# MainBoard.net
KiCad netlist of a schematic drawn in Altium Designer
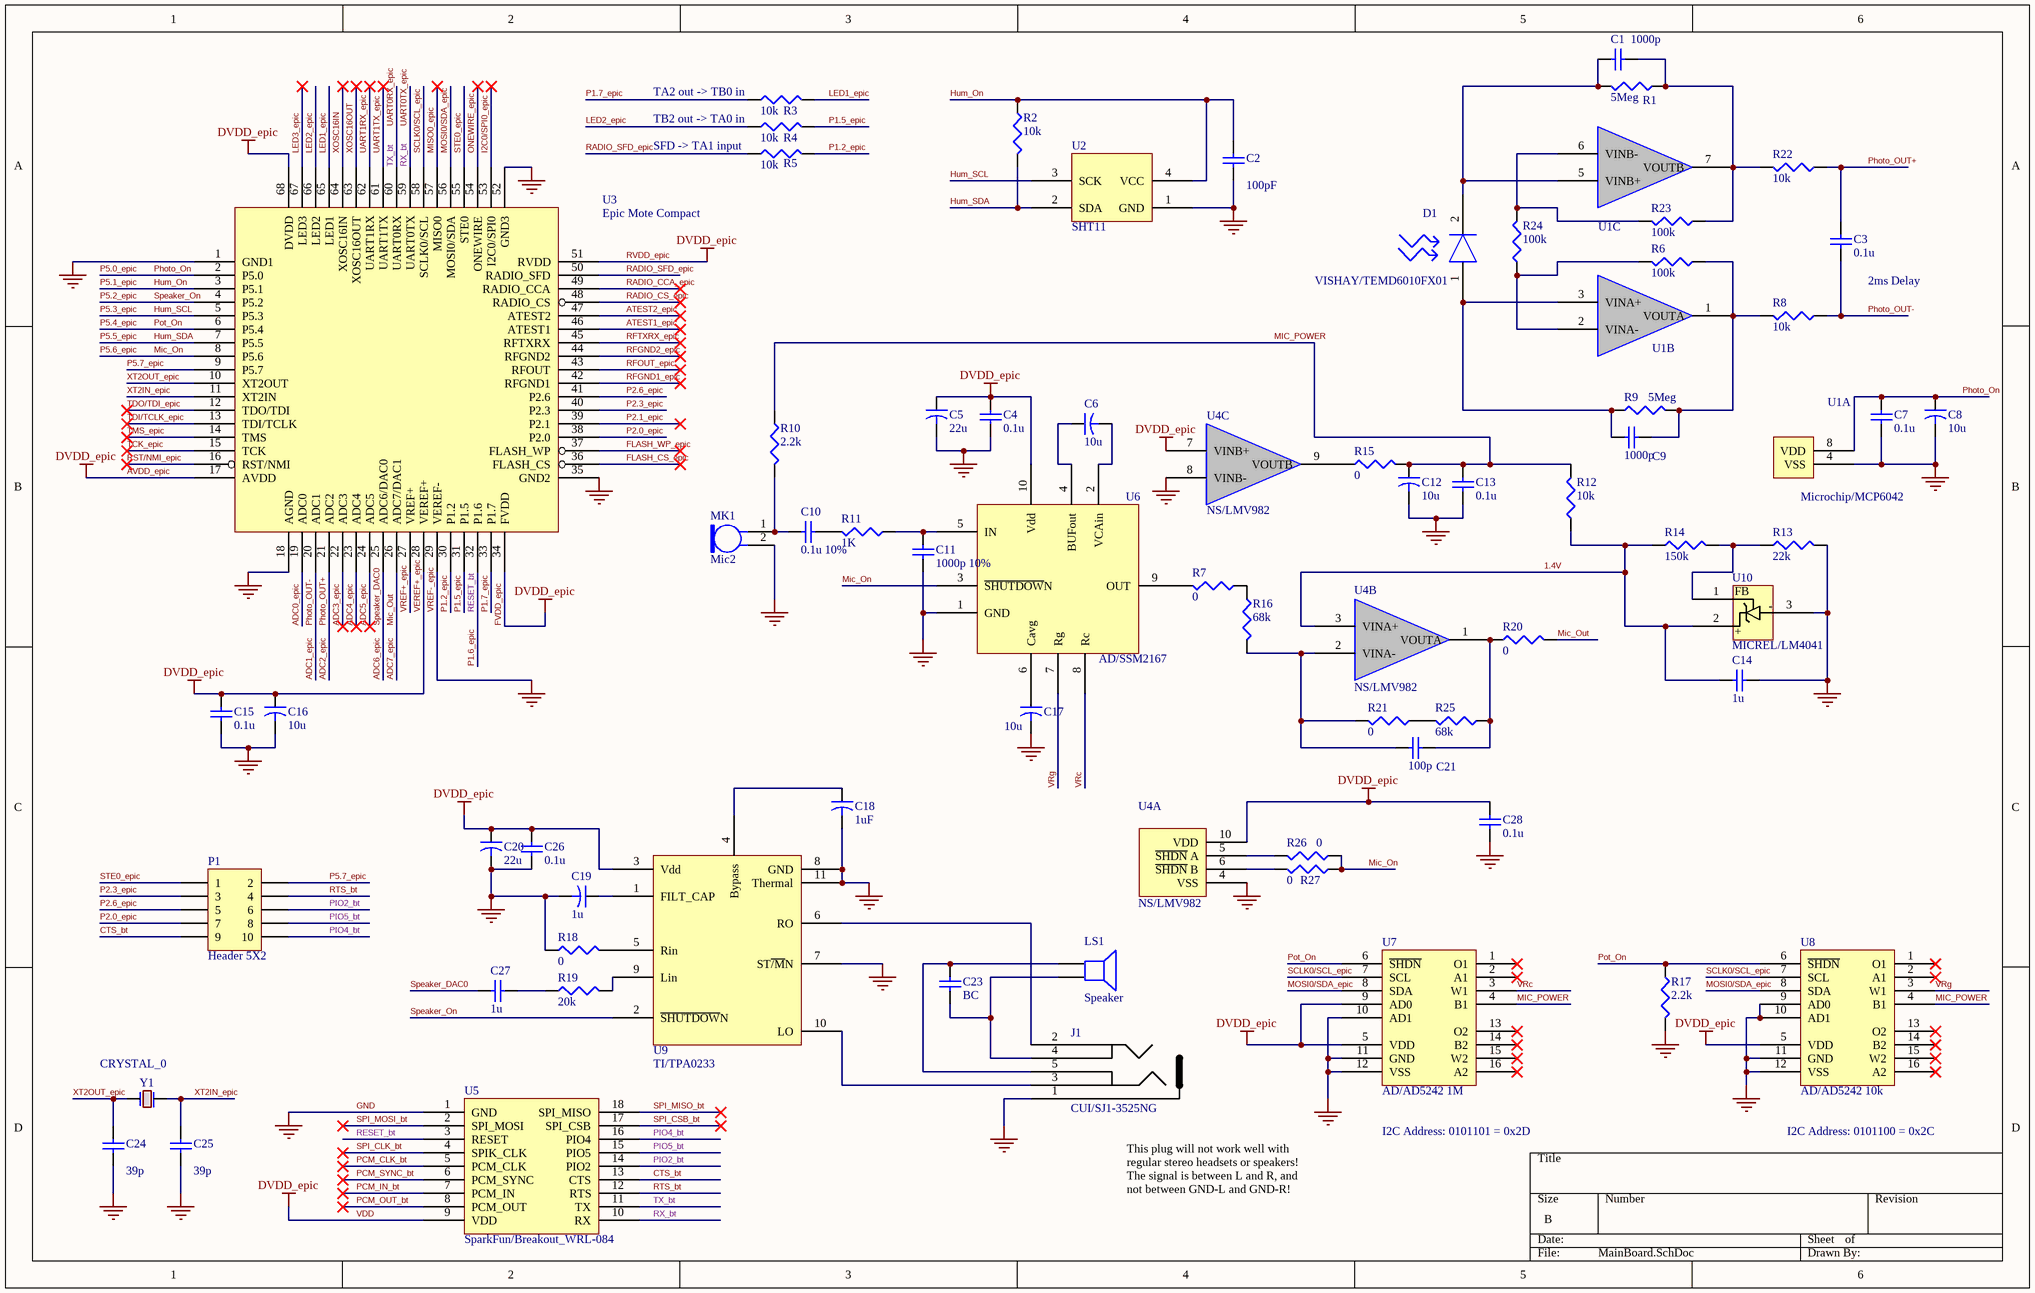
[diagram p0: MainBoard.SchDoc]

(export (version "E")
  (design (tool "Eeschema 10.0.6"))
  (components
    (comp (ref "C1")
      (value "1000p")
      (footprint "CC1608-0603")
      (description "Capacitor")
      (fields (field (name "Comment") "Cap") (field (name "PUBLISHER") "Altium Limited"))
      (libsource (lib "Miscellaneous Devices") (part "Cap"))
    )
    (comp (ref "C2")
      (value "100pF")
      (footprint "CC1608-0603")
      (description "Capacitor")
      (fields (field (name "Comment") "Cap") (field (name "PUBLISHER") "Altium Limited"))
      (libsource (lib "Miscellaneous Devices") (part "Cap"))
    )
    (comp (ref "C3")
      (value "0.1u")
      (footprint "CC1608-0603")
      (description "Capacitor")
      (fields (field (name "Comment") "Cap") (field (name "PUBLISHER") "Altium Limited"))
      (libsource (lib "Miscellaneous Devices") (part "Cap"))
    )
    (comp (ref "C4")
      (value "0.1u")
      (footprint "CC1608-0603")
      (description "Capacitor")
      (fields (field (name "Comment") "Cap") (field (name "PUBLISHER") "Altium Limited"))
      (libsource (lib "Miscellaneous Devices") (part "Cap"))
    )
    (comp (ref "C5")
      (value "22u")
      (footprint "CC3216-1206")
      (description "Capacitor")
      (fields (field (name "Comment") "Cap2") (field (name "PUBLISHER") "Altium Limited"))
      (libsource (lib "Miscellaneous Devices") (part "Cap2"))
    )
    (comp (ref "C6")
      (value "10u")
      (footprint "CC1608-0603")
      (description "Capacitor")
      (fields (field (name "Comment") "Cap2") (field (name "PUBLISHER") "Altium Limited"))
      (libsource (lib "") (part "Cap2_1"))
    )
    (comp (ref "C7")
      (value "0.1u")
      (footprint "CC1608-0603")
      (description "Capacitor")
      (fields (field (name "Comment") "Cap") (field (name "PUBLISHER") "Altium Limited"))
      (libsource (lib "Miscellaneous Devices") (part "Cap"))
    )
    (comp (ref "C8")
      (value "10u")
      (footprint "CC1608-0603")
      (description "Capacitor")
      (fields (field (name "Comment") "Cap2") (field (name "PUBLISHER") "Altium Limited"))
      (libsource (lib "Miscellaneous Devices") (part "Cap2"))
    )
    (comp (ref "C9")
      (value "1000p")
      (footprint "CC1608-0603")
      (description "Capacitor")
      (fields (field (name "Comment") "Cap") (field (name "PUBLISHER") "Altium Limited"))
      (libsource (lib "Miscellaneous Devices") (part "Cap"))
    )
    (comp (ref "C10")
      (value "0.1u 10%")
      (footprint "CC1608-0603")
      (description "Capacitor")
      (fields (field (name "Comment") "Cap") (field (name "PUBLISHER") "Altium Limited"))
      (libsource (lib "Miscellaneous Devices") (part "Cap"))
    )
    (comp (ref "C11")
      (value "1000p 10%")
      (footprint "CC1608-0603")
      (description "Capacitor")
      (fields (field (name "Comment") "Cap") (field (name "PUBLISHER") "Altium Limited"))
      (libsource (lib "Miscellaneous Devices") (part "Cap"))
    )
    (comp (ref "C12")
      (value "10u")
      (footprint "CC1608-0603")
      (description "Capacitor")
      (fields (field (name "Comment") "Cap2") (field (name "PUBLISHER") "Altium Limited"))
      (libsource (lib "Miscellaneous Devices") (part "Cap2"))
    )
    (comp (ref "C13")
      (value "0.1u")
      (footprint "CC1608-0603")
      (description "Capacitor")
      (fields (field (name "Comment") "Cap") (field (name "PUBLISHER") "Altium Limited"))
      (libsource (lib "Miscellaneous Devices") (part "Cap"))
    )
    (comp (ref "C14")
      (value "1u")
      (footprint "CC1608-0603")
      (description "Capacitor")
      (fields (field (name "Comment") "Cap") (field (name "PUBLISHER") "Altium Limited"))
      (libsource (lib "") (part "Cap_1"))
    )
    (comp (ref "C15")
      (value "0.1u")
      (footprint "CC1608-0603")
      (description "Capacitor")
      (fields (field (name "Comment") "Cap") (field (name "PUBLISHER") "Altium Limited"))
      (libsource (lib "Miscellaneous Devices") (part "Cap"))
    )
    (comp (ref "C16")
      (value "10u")
      (footprint "CC1608-0603")
      (description "Capacitor")
      (fields (field (name "Comment") "Cap2") (field (name "PUBLISHER") "Altium Limited"))
      (libsource (lib "Miscellaneous Devices") (part "Cap2"))
    )
    (comp (ref "C17")
      (value "10u")
      (footprint "CC1608-0603")
      (description "Capacitor")
      (fields (field (name "Comment") "Cap2") (field (name "PUBLISHER") "Altium Limited"))
      (libsource (lib "") (part "Cap2_1"))
    )
    (comp (ref "C18")
      (value "1uF")
      (footprint "CC1608-0603")
      (description "Capacitor")
      (fields (field (name "Comment") "Cap2") (field (name "PUBLISHER") "Altium Limited"))
      (libsource (lib "") (part "Cap2_1"))
    )
    (comp (ref "C19")
      (value "1u")
      (footprint "CC1608-0603")
      (description "Capacitor")
      (fields (field (name "Comment") "Cap2") (field (name "PUBLISHER") "Altium Limited"))
      (libsource (lib "") (part "Cap2_1"))
    )
    (comp (ref "C20")
      (value "22u")
      (footprint "CC3216-1206")
      (description "Capacitor")
      (fields (field (name "Comment") "Cap2") (field (name "PUBLISHER") "Altium Limited"))
      (libsource (lib "Miscellaneous Devices") (part "Cap2"))
    )
    (comp (ref "C21")
      (value "100p")
      (footprint "CC1608-0603")
      (description "Capacitor")
      (fields (field (name "Comment") "Cap") (field (name "PUBLISHER") "Altium Limited"))
      (libsource (lib "Miscellaneous Devices") (part "Cap"))
    )
    (comp (ref "C23")
      (value "BC")
      (footprint "CC1608-0603")
      (description "Capacitor")
      (fields (field (name "Comment") "Cap") (field (name "PUBLISHER") "Altium Limited"))
      (libsource (lib "Miscellaneous Devices") (part "Cap"))
    )
    (comp (ref "C24")
      (value "39p")
      (footprint "CC1608-0603")
      (description "Capacitor")
      (fields (field (name "Comment") "Cap") (field (name "PUBLISHER") "Altium Limited"))
      (libsource (lib "Miscellaneous Devices") (part "Cap"))
    )
    (comp (ref "C25")
      (value "39p")
      (footprint "CC1608-0603")
      (description "Capacitor")
      (fields (field (name "Comment") "Cap") (field (name "PUBLISHER") "Altium Limited"))
      (libsource (lib "Miscellaneous Devices") (part "Cap"))
    )
    (comp (ref "C26")
      (value "0.1u")
      (footprint "CC1608-0603")
      (description "Capacitor")
      (fields (field (name "Comment") "Cap") (field (name "PUBLISHER") "Altium Limited"))
      (libsource (lib "Miscellaneous Devices") (part "Cap"))
    )
    (comp (ref "C27")
      (value "1u")
      (footprint "CC1608-0603")
      (description "Capacitor")
      (fields (field (name "Comment") "Cap") (field (name "PUBLISHER") "Altium Limited"))
      (libsource (lib "Miscellaneous Devices") (part "Cap"))
    )
    (comp (ref "C28")
      (value "0.1u")
      (footprint "CC1608-0603")
      (description "Capacitor")
      (fields (field (name "Comment") "Cap") (field (name "PUBLISHER") "Altium Limited"))
      (libsource (lib "Miscellaneous Devices") (part "Cap"))
    )
    (comp (ref "D1")
      (value "VISHAY/TEMD6010FX01")
      (footprint "VISHAY/TEMD6010FX01")
      (libsource (lib "Schematics") (part "VISHAY/TEMD6010FX01"))
    )
    (comp (ref "J1")
      (value "CUI/SJ1-3525NG")
      (footprint "CUI/PHONE_JACK_3.5mm")
      (libsource (lib "Schematics") (part "CUI/SJ1-3525NG"))
    )
    (comp (ref "LS1")
      (value "Speaker")
      (footprint "PIN2")
      (description "Loudspeaker")
      (fields (field (name "PUBLISHER") "Altium Limited"))
      (libsource (lib "Miscellaneous Devices") (part "Speaker"))
    )
    (comp (ref "MK1")
      (value "Mic2")
      (footprint "CUIINC/CMA-4544PF-W")
      (description "Microphone")
      (fields (field (name "PUBLISHER") "Altium Limited"))
      (libsource (lib "Miscellaneous Devices") (part "Mic2"))
    )
    (comp (ref "P1")
      (value "Header 5X2")
      (footprint "HDR2X5")
      (description "Header, 5-Pin, Dual row")
      (fields (field (name "PUBLISHER") "Altium Limited"))
      (libsource (lib "Miscellaneous Connectors") (part "Header 5X2"))
    )
    (comp (ref "R1")
      (value "5Meg")
      (footprint "CR1608-0603")
      (description "Resistor")
      (fields (field (name "Comment") "Res3") (field (name "PUBLISHER") "Altium Limited"))
      (libsource (lib "Miscellaneous Devices") (part "Res3"))
    )
    (comp (ref "R2")
      (value "10k")
      (footprint "CR1608-0603")
      (description "Resistor")
      (fields (field (name "Comment") "Res3") (field (name "PUBLISHER") "Altium Limited"))
      (libsource (lib "Miscellaneous Devices") (part "Res3"))
    )
    (comp (ref "R3")
      (value "10k")
      (footprint "CR1608-0603")
      (description "Resistor")
      (fields (field (name "Comment") "Res3") (field (name "PUBLISHER") "Altium Limited"))
      (libsource (lib "Miscellaneous Devices") (part "Res3"))
    )
    (comp (ref "R4")
      (value "10k")
      (footprint "CR1608-0603")
      (description "Resistor")
      (fields (field (name "Comment") "Res3") (field (name "PUBLISHER") "Altium Limited"))
      (libsource (lib "Miscellaneous Devices") (part "Res3"))
    )
    (comp (ref "R5")
      (value "10k")
      (footprint "CR1608-0603")
      (description "Resistor")
      (fields (field (name "Comment") "Res3") (field (name "PUBLISHER") "Altium Limited"))
      (libsource (lib "Miscellaneous Devices") (part "Res3"))
    )
    (comp (ref "R6")
      (value "100k")
      (footprint "CR1608-0603")
      (description "Resistor")
      (fields (field (name "Comment") "Res3") (field (name "PUBLISHER") "Altium Limited"))
      (libsource (lib "Miscellaneous Devices") (part "Res3"))
    )
    (comp (ref "R7")
      (value "0")
      (footprint "CR1608-0603")
      (description "Resistor")
      (fields (field (name "Comment") "Res3") (field (name "PUBLISHER") "Altium Limited"))
      (libsource (lib "Miscellaneous Devices") (part "Res3"))
    )
    (comp (ref "R8")
      (value "10k")
      (footprint "CR1608-0603")
      (description "Resistor")
      (fields (field (name "Comment") "Res3") (field (name "PUBLISHER") "Altium Limited"))
      (libsource (lib "Miscellaneous Devices") (part "Res3"))
    )
    (comp (ref "R9")
      (value "5Meg")
      (footprint "CR1608-0603")
      (description "Resistor")
      (fields (field (name "Comment") "Res3") (field (name "PUBLISHER") "Altium Limited"))
      (libsource (lib "Miscellaneous Devices") (part "Res3"))
    )
    (comp (ref "R10")
      (value "2.2k")
      (footprint "CR1608-0603")
      (description "Resistor")
      (fields (field (name "Comment") "Res3") (field (name "PUBLISHER") "Altium Limited"))
      (libsource (lib "Miscellaneous Devices") (part "Res3"))
    )
    (comp (ref "R11")
      (value "1K")
      (footprint "CR1608-0603")
      (description "Resistor")
      (fields (field (name "Comment") "Res3") (field (name "PUBLISHER") "Altium Limited"))
      (libsource (lib "Miscellaneous Devices") (part "Res3"))
    )
    (comp (ref "R12")
      (value "10k")
      (footprint "CR1608-0603")
      (description "Resistor")
      (fields (field (name "Comment") "Res3") (field (name "PUBLISHER") "Altium Limited"))
      (libsource (lib "Miscellaneous Devices") (part "Res3"))
    )
    (comp (ref "R13")
      (value "22k")
      (footprint "CR1608-0603")
      (description "Resistor")
      (fields (field (name "Comment") "Res3") (field (name "PUBLISHER") "Altium Limited"))
      (libsource (lib "Miscellaneous Devices") (part "Res3"))
    )
    (comp (ref "R14")
      (value "150k")
      (footprint "CR1608-0603")
      (description "Resistor")
      (fields (field (name "Comment") "Res3") (field (name "PUBLISHER") "Altium Limited"))
      (libsource (lib "Miscellaneous Devices") (part "Res3"))
    )
    (comp (ref "R15")
      (value "0")
      (footprint "CR1608-0603")
      (description "Resistor")
      (fields (field (name "Comment") "Res3") (field (name "PUBLISHER") "Altium Limited"))
      (libsource (lib "Miscellaneous Devices") (part "Res3"))
    )
    (comp (ref "R16")
      (value "68k")
      (footprint "CR1608-0603")
      (description "Resistor")
      (fields (field (name "Comment") "Res3") (field (name "PUBLISHER") "Altium Limited"))
      (libsource (lib "") (part "Res3_1"))
    )
    (comp (ref "R17")
      (value "2.2k")
      (footprint "CR1608-0603")
      (description "Resistor")
      (fields (field (name "Comment") "Res3") (field (name "PUBLISHER") "Altium Limited"))
      (libsource (lib "Miscellaneous Devices") (part "Res3"))
    )
    (comp (ref "R18")
      (value "0")
      (footprint "CR1608-0603")
      (description "Resistor")
      (fields (field (name "Comment") "Res3") (field (name "PUBLISHER") "Altium Limited"))
      (libsource (lib "Miscellaneous Devices") (part "Res3"))
    )
    (comp (ref "R19")
      (value "20k")
      (footprint "CR1608-0603")
      (description "Resistor")
      (fields (field (name "Comment") "Res3") (field (name "PUBLISHER") "Altium Limited"))
      (libsource (lib "Miscellaneous Devices") (part "Res3"))
    )
    (comp (ref "R20")
      (value "0")
      (footprint "CR1608-0603")
      (description "Resistor")
      (fields (field (name "Comment") "Res3") (field (name "PUBLISHER") "Altium Limited"))
      (libsource (lib "Miscellaneous Devices") (part "Res3"))
    )
    (comp (ref "R21")
      (value "0")
      (footprint "CR1608-0603")
      (description "Resistor")
      (fields (field (name "Comment") "Res3") (field (name "PUBLISHER") "Altium Limited"))
      (libsource (lib "Miscellaneous Devices") (part "Res3"))
    )
    (comp (ref "R22")
      (value "10k")
      (footprint "CR1608-0603")
      (description "Resistor")
      (fields (field (name "Comment") "Res3") (field (name "PUBLISHER") "Altium Limited"))
      (libsource (lib "Miscellaneous Devices") (part "Res3"))
    )
    (comp (ref "R23")
      (value "100k")
      (footprint "CR1608-0603")
      (description "Resistor")
      (fields (field (name "Comment") "Res3") (field (name "PUBLISHER") "Altium Limited"))
      (libsource (lib "Miscellaneous Devices") (part "Res3"))
    )
    (comp (ref "R24")
      (value "100k")
      (footprint "CR1608-0603")
      (description "Resistor")
      (fields (field (name "Comment") "Res3") (field (name "PUBLISHER") "Altium Limited"))
      (libsource (lib "Miscellaneous Devices") (part "Res3"))
    )
    (comp (ref "R25")
      (value "68k")
      (footprint "CR1608-0603")
      (description "Resistor")
      (fields (field (name "Comment") "Res3") (field (name "PUBLISHER") "Altium Limited"))
      (libsource (lib "Miscellaneous Devices") (part "Res3"))
    )
    (comp (ref "R26")
      (value "0")
      (footprint "CR1608-0603")
      (description "Resistor")
      (fields (field (name "Comment") "Res3") (field (name "PUBLISHER") "Altium Limited"))
      (libsource (lib "Miscellaneous Devices") (part "Res3"))
    )
    (comp (ref "R27")
      (value "0")
      (footprint "CR1608-0603")
      (description "Resistor")
      (fields (field (name "Comment") "Res3") (field (name "PUBLISHER") "Altium Limited"))
      (libsource (lib "Miscellaneous Devices") (part "Res3"))
    )
    (comp (ref "U1")
      (value "Microchip/MCP6042")
      (footprint "SOIC127P600X175-8N")
      (libsource (lib "Schematics") (part "Microchip/MCP6042"))
    )
    (comp (ref "U2")
      (value "SHT11")
      (footprint "Sensirion/SHT11")
      (libsource (lib "Schematics") (part "SHT11"))
    )
    (comp (ref "U3")
      (value "Epic Mote Compact")
      (footprint "UCB/Epic_Quanto_Header")
      (libsource (lib "Schematics") (part "Epic Mote Compact"))
    )
    (comp (ref "U4")
      (value "NS/LMV982")
      (footprint "MSOP10")
      (libsource (lib "Schematics") (part "NS/LMV982"))
    )
    (comp (ref "U5")
      (value "SparkFun/Breakout_WRL-084")
      (footprint "SparkFun/Breakout_WRL-084")
      (libsource (lib "Schematics") (part "SparkFun/Breakout_WRL-084"))
    )
    (comp (ref "U6")
      (value "AD/SSM2167")
      (footprint "MSOP127P600-8N")
      (libsource (lib "Schematics") (part "AD/SSM2167"))
    )
    (comp (ref "U7")
      (value "AD/AD5242 1M")
      (footprint "SOIC127P600X175-16N")
      (libsource (lib "Schematics") (part "AD/AD5242"))
    )
    (comp (ref "U8")
      (value "AD/AD5242 10k")
      (footprint "SOIC127P600X175-16N")
      (libsource (lib "Schematics") (part "AD/AD5242"))
    )
    (comp (ref "U9")
      (value "TI/TPA0233")
      (footprint "TSSOP50P480X107_HS-10N")
      (libsource (lib "Schematics") (part "TI/TPA0233"))
    )
    (comp (ref "U10")
      (value "MICREL/LM4041")
      (footprint "SOT231 (M3)")
      (libsource (lib "Schematics") (part "MICREL/LM4041"))
    )
    (comp (ref "Y1")
      (value "CRYSTAL_0")
      (footprint "ECS/CSM-7SSX")
      (libsource (lib "Schematics") (part "CRYSTAL_0"))
    )
  )
  (nets
    (net (code "1") (name "/1.4V") (class "Default")
      (node (ref "C14") (pin "1") (pinfunction "1_1") (pintype "passive"))
      (node (ref "R12") (pin "1") (pinfunction "1_1") (pintype "passive"))
      (node (ref "R14") (pin "1") (pinfunction "1_1") (pintype "passive"))
      (node (ref "U10") (pin "2") (pinfunction "2_2") (pintype "passive"))
      (node (ref "U4") (pin "3") (pinfunction "VINA+_3") (pintype "passive"))
    )
    (net (code "2") (name "/ADC0_epic") (class "Default")
      (node (ref "U3") (pin "19") (pinfunction "ADC0_19") (pintype "passive"))
    )
    (net (code "3") (name "/ADC1_epic") (class "Default")
      (node (ref "C3") (pin "2") (pinfunction "2_2") (pintype "passive"))
      (node (ref "R8") (pin "1") (pinfunction "1_1") (pintype "passive"))
      (node (ref "U3") (pin "20") (pinfunction "ADC1_20") (pintype "passive"))
    )
    (net (code "4") (name "/ADC2_epic") (class "Default")
      (node (ref "C3") (pin "1") (pinfunction "1_1") (pintype "passive"))
      (node (ref "R22") (pin "1") (pinfunction "1_1") (pintype "passive"))
      (node (ref "U3") (pin "21") (pinfunction "ADC2_21") (pintype "passive"))
    )
    (net (code "5") (name "/ADC3_epic") (class "Default")
      (node (ref "U3") (pin "22") (pinfunction "ADC3_22") (pintype "passive+no_connect"))
    )
    (net (code "6") (name "/ADC4_epic") (class "Default")
      (node (ref "U3") (pin "23") (pinfunction "ADC4_23") (pintype "passive+no_connect"))
    )
    (net (code "7") (name "/ADC5_epic") (class "Default")
      (node (ref "U3") (pin "24") (pinfunction "ADC5_24") (pintype "passive+no_connect"))
    )
    (net (code "8") (name "/ADC6_epic") (class "Default")
      (node (ref "C27") (pin "2") (pinfunction "2_2") (pintype "passive"))
      (node (ref "U3") (pin "25") (pinfunction "ADC6/DAC0_25") (pintype "passive"))
    )
    (net (code "9") (name "/ADC7_epic") (class "Default")
      (node (ref "R20") (pin "2") (pinfunction "2_2") (pintype "passive"))
      (node (ref "U3") (pin "26") (pinfunction "ADC7/DAC1_26") (pintype "passive"))
    )
    (net (code "10") (name "/ATEST1_epic") (class "Default")
      (node (ref "U3") (pin "46") (pinfunction "ATEST1_46") (pintype "passive+no_connect"))
    )
    (net (code "11") (name "/ATEST2_epic") (class "Default")
      (node (ref "U3") (pin "47") (pinfunction "ATEST2_47") (pintype "passive+no_connect"))
    )
    (net (code "12") (name "/CTS_bt") (class "Default")
      (node (ref "P1") (pin "9") (pinfunction "9_9") (pintype "passive"))
      (node (ref "U5") (pin "13") (pinfunction "CTS_13") (pintype "passive"))
    )
    (net (code "13") (name "/FLASH_CS_epic") (class "Default")
      (node (ref "U3") (pin "36") (pinfunction "FLASH_CS_36") (pintype "passive+no_connect"))
    )
    (net (code "14") (name "/FLASH_WP_epic") (class "Default")
      (node (ref "U3") (pin "37") (pinfunction "FLASH_WP_37") (pintype "passive+no_connect"))
    )
    (net (code "15") (name "/Hum_On") (class "Default")
      (node (ref "C2") (pin "2") (pinfunction "2_2") (pintype "passive"))
      (node (ref "R2") (pin "1") (pinfunction "1_1") (pintype "passive"))
      (node (ref "U2") (pin "4") (pinfunction "VCC_4") (pintype "power_in"))
      (node (ref "U3") (pin "3") (pinfunction "P5.1_3") (pintype "passive"))
    )
    (net (code "16") (name "/Hum_SCL") (class "Default")
      (node (ref "U2") (pin "3") (pinfunction "SCK_3") (pintype "passive"))
      (node (ref "U3") (pin "5") (pinfunction "P5.3_5") (pintype "passive"))
    )
    (net (code "17") (name "/Hum_SDA") (class "Default")
      (node (ref "R2") (pin "2") (pinfunction "2_2") (pintype "passive"))
      (node (ref "U2") (pin "2") (pinfunction "SDA_2") (pintype "passive"))
      (node (ref "U3") (pin "7") (pinfunction "P5.5_7") (pintype "passive"))
    )
    (net (code "18") (name "/I2C0{slash}SPI0_epic") (class "Default")
      (node (ref "U3") (pin "53") (pinfunction "I2C0/SPI0_53") (pintype "passive+no_connect"))
    )
    (net (code "19") (name "/LED1_epic") (class "Default")
      (node (ref "R3") (pin "2") (pinfunction "2_2") (pintype "passive"))
      (node (ref "U3") (pin "65") (pinfunction "LED1_65") (pintype "passive"))
    )
    (net (code "20") (name "/LED2_epic") (class "Default")
      (node (ref "R4") (pin "1") (pinfunction "1_1") (pintype "passive"))
      (node (ref "U3") (pin "66") (pinfunction "LED2_66") (pintype "passive"))
    )
    (net (code "21") (name "/LED3_epic") (class "Default")
      (node (ref "U3") (pin "67") (pinfunction "LED3_67") (pintype "passive+no_connect"))
    )
    (net (code "22") (name "/MIC_POWER") (class "Default")
      (node (ref "C12") (pin "1") (pinfunction "1_1") (pintype "passive"))
      (node (ref "C13") (pin "1") (pinfunction "1_1") (pintype "passive"))
      (node (ref "R10") (pin "1") (pinfunction "1_1") (pintype "passive"))
      (node (ref "R12") (pin "2") (pinfunction "2_2") (pintype "passive"))
      (node (ref "R15") (pin "2") (pinfunction "2_2") (pintype "passive"))
      (node (ref "U7") (pin "4") (pinfunction "B1_4") (pintype "passive"))
      (node (ref "U8") (pin "4") (pinfunction "B1_4") (pintype "passive"))
    )
    (net (code "23") (name "/MISO0_epic") (class "Default")
      (node (ref "U3") (pin "57") (pinfunction "MISO0_57") (pintype "passive+no_connect"))
    )
    (net (code "24") (name "/MOSI0{slash}SDA_epic") (class "Default")
      (node (ref "U3") (pin "56") (pinfunction "MOSI0/SDA_56") (pintype "passive"))
      (node (ref "U7") (pin "8") (pinfunction "SDA_8") (pintype "passive"))
      (node (ref "U8") (pin "8") (pinfunction "SDA_8") (pintype "passive"))
    )
    (net (code "25") (name "/Mic_On") (class "Default")
      (node (ref "R26") (pin "2") (pinfunction "2_2") (pintype "passive"))
      (node (ref "R27") (pin "2") (pinfunction "2_2") (pintype "passive"))
      (node (ref "U3") (pin "8") (pinfunction "P5.6_8") (pintype "passive"))
      (node (ref "U6") (pin "3") (pinfunction "~{SHUTDOW}N_3") (pintype "passive"))
    )
    (net (code "26") (name "/ONEWIRE_epic") (class "Default")
      (node (ref "U3") (pin "54") (pinfunction "ONEWIRE_54") (pintype "passive+no_connect"))
    )
    (net (code "27") (name "/P1.2_epic") (class "Default")
      (node (ref "R5") (pin "2") (pinfunction "2_2") (pintype "passive"))
      (node (ref "U3") (pin "30") (pinfunction "P1.2_30") (pintype "passive"))
    )
    (net (code "28") (name "/P1.5_epic") (class "Default")
      (node (ref "R4") (pin "2") (pinfunction "2_2") (pintype "passive"))
      (node (ref "U3") (pin "31") (pinfunction "P1.5_31") (pintype "passive"))
    )
    (net (code "29") (name "/P1.6_epic") (class "Default")
      (node (ref "U3") (pin "32") (pinfunction "P1.6_32") (pintype "passive"))
      (node (ref "U5") (pin "3") (pinfunction "RESET_3") (pintype "passive"))
    )
    (net (code "30") (name "/P1.7_epic") (class "Default")
      (node (ref "R3") (pin "1") (pinfunction "1_1") (pintype "passive"))
      (node (ref "U3") (pin "33") (pinfunction "P1.7_33") (pintype "passive"))
    )
    (net (code "31") (name "/P2.0_epic") (class "Default")
      (node (ref "P1") (pin "7") (pinfunction "7_7") (pintype "passive"))
      (node (ref "U3") (pin "38") (pinfunction "P2.0_38") (pintype "passive"))
    )
    (net (code "32") (name "/P2.1_epic") (class "Default")
      (node (ref "U3") (pin "39") (pinfunction "P2.1_39") (pintype "passive+no_connect"))
    )
    (net (code "33") (name "/P2.3_epic") (class "Default")
      (node (ref "P1") (pin "3") (pinfunction "3_3") (pintype "passive"))
      (node (ref "U3") (pin "40") (pinfunction "P2.3_40") (pintype "passive"))
    )
    (net (code "34") (name "/P2.6_epic") (class "Default")
      (node (ref "P1") (pin "5") (pinfunction "5_5") (pintype "passive"))
      (node (ref "U3") (pin "41") (pinfunction "P2.6_41") (pintype "passive"))
    )
    (net (code "35") (name "/P5.0_epic") (class "Default")
      (node (ref "C7") (pin "1") (pinfunction "1_1") (pintype "passive"))
      (node (ref "C8") (pin "1") (pinfunction "1_1") (pintype "passive"))
      (node (ref "U1") (pin "8") (pinfunction "VDD_8") (pintype "power_in"))
      (node (ref "U3") (pin "2") (pinfunction "P5.0_2") (pintype "passive"))
    )
    (net (code "36") (name "/P5.2_epic") (class "Default")
      (node (ref "U3") (pin "4") (pinfunction "P5.2_4") (pintype "passive"))
      (node (ref "U9") (pin "2") (pinfunction "~{SHUTDOW}N_2") (pintype "passive"))
    )
    (net (code "37") (name "/P5.4_epic") (class "Default")
      (node (ref "R17") (pin "1") (pinfunction "1_1") (pintype "passive"))
      (node (ref "U3") (pin "6") (pinfunction "P5.4_6") (pintype "passive"))
      (node (ref "U7") (pin "6") (pinfunction "~{SHDN}_6") (pintype "passive"))
      (node (ref "U8") (pin "6") (pinfunction "~{SHDN}_6") (pintype "passive"))
    )
    (net (code "38") (name "/P5.7_epic") (class "Default")
      (node (ref "P1") (pin "2") (pinfunction "2_2") (pintype "passive"))
      (node (ref "U3") (pin "9") (pinfunction "P5.7_9") (pintype "passive"))
    )
    (net (code "39") (name "/PCM_CLK_bt") (class "Default")
      (node (ref "U5") (pin "5") (pinfunction "PCM_CLK_5") (pintype "passive+no_connect"))
    )
    (net (code "40") (name "/PCM_IN_bt") (class "Default")
      (node (ref "U5") (pin "7") (pinfunction "PCM_IN_7") (pintype "passive+no_connect"))
    )
    (net (code "41") (name "/PCM_OUT_bt") (class "Default")
      (node (ref "U5") (pin "8") (pinfunction "PCM_OUT_8") (pintype "passive+no_connect"))
    )
    (net (code "42") (name "/PCM_SYNC_bt") (class "Default")
      (node (ref "U5") (pin "6") (pinfunction "PCM_SYNC_6") (pintype "passive+no_connect"))
    )
    (net (code "43") (name "/PIO2_bt") (class "Default")
      (node (ref "P1") (pin "6") (pinfunction "6_6") (pintype "passive"))
      (node (ref "U5") (pin "14") (pinfunction "PIO2_14") (pintype "passive"))
    )
    (net (code "44") (name "/PIO4_bt") (class "Default")
      (node (ref "P1") (pin "10") (pinfunction "10_10") (pintype "passive"))
      (node (ref "U5") (pin "16") (pinfunction "PIO4_16") (pintype "passive"))
    )
    (net (code "45") (name "/PIO5_bt") (class "Default")
      (node (ref "P1") (pin "8") (pinfunction "8_8") (pintype "passive"))
      (node (ref "U5") (pin "15") (pinfunction "PIO5_15") (pintype "passive"))
    )
    (net (code "46") (name "/RADIO_CCA_epic") (class "Default")
      (node (ref "U3") (pin "49") (pinfunction "RADIO_CCA_49") (pintype "passive+no_connect"))
    )
    (net (code "47") (name "/RADIO_CS_epic") (class "Default")
      (node (ref "U3") (pin "48") (pinfunction "RADIO_CS_48") (pintype "passive+no_connect"))
    )
    (net (code "48") (name "/RADIO_SFD_epic") (class "Default")
      (node (ref "R5") (pin "1") (pinfunction "1_1") (pintype "passive"))
      (node (ref "U3") (pin "50") (pinfunction "RADIO_SFD_50") (pintype "passive"))
    )
    (net (code "49") (name "/RFGND1_epic") (class "Default")
      (node (ref "U3") (pin "42") (pinfunction "RFGND1_42") (pintype "passive+no_connect"))
    )
    (net (code "50") (name "/RFGND2_epic") (class "Default")
      (node (ref "U3") (pin "44") (pinfunction "RFGND2_44") (pintype "passive+no_connect"))
    )
    (net (code "51") (name "/RFOUT_epic") (class "Default")
      (node (ref "U3") (pin "43") (pinfunction "RFOUT_43") (pintype "passive+no_connect"))
    )
    (net (code "52") (name "/RFTXRX_epic") (class "Default")
      (node (ref "U3") (pin "45") (pinfunction "RFTXRX_45") (pintype "passive+no_connect"))
    )
    (net (code "53") (name "/RST{slash}NMI_epic") (class "Default")
      (node (ref "U3") (pin "16") (pinfunction "RST/NMI_16") (pintype "passive+no_connect"))
    )
    (net (code "54") (name "/RTS_bt") (class "Default")
      (node (ref "P1") (pin "4") (pinfunction "4_4") (pintype "passive"))
      (node (ref "U5") (pin "12") (pinfunction "RTS_12") (pintype "passive"))
    )
    (net (code "55") (name "/RX_bt") (class "Default")
      (node (ref "U3") (pin "59") (pinfunction "UART0TX_59") (pintype "passive"))
      (node (ref "U5") (pin "10") (pinfunction "RX_10") (pintype "passive"))
    )
    (net (code "56") (name "/SCLK0{slash}SCL_epic") (class "Default")
      (node (ref "U3") (pin "58") (pinfunction "SCLK0/SCL_58") (pintype "passive"))
      (node (ref "U7") (pin "7") (pinfunction "SCL_7") (pintype "passive"))
      (node (ref "U8") (pin "7") (pinfunction "SCL_7") (pintype "passive"))
    )
    (net (code "57") (name "/SPI_CLK_bt") (class "Default")
      (node (ref "U5") (pin "4") (pinfunction "SPIK_CLK_4") (pintype "passive+no_connect"))
    )
    (net (code "58") (name "/SPI_CSB_bt") (class "Default")
      (node (ref "U5") (pin "17") (pinfunction "SPI_CSB_17") (pintype "passive+no_connect"))
    )
    (net (code "59") (name "/SPI_MISO_bt") (class "Default")
      (node (ref "U5") (pin "18") (pinfunction "SPI_MISO_18") (pintype "passive+no_connect"))
    )
    (net (code "60") (name "/SPI_MOSI_bt") (class "Default")
      (node (ref "U5") (pin "2") (pinfunction "SPI_MOSI_2") (pintype "passive+no_connect"))
    )
    (net (code "61") (name "/STE0_epic") (class "Default")
      (node (ref "P1") (pin "1") (pinfunction "1_1") (pintype "passive"))
      (node (ref "U3") (pin "55") (pinfunction "STE0_55") (pintype "passive"))
    )
    (net (code "62") (name "/TCK_epic") (class "Default")
      (node (ref "U3") (pin "15") (pinfunction "TCK_15") (pintype "passive+no_connect"))
    )
    (net (code "63") (name "/TDI{slash}TCLK_epic") (class "Default")
      (node (ref "U3") (pin "13") (pinfunction "TDI/TCLK_13") (pintype "passive+no_connect"))
    )
    (net (code "64") (name "/TDO{slash}TDI_epic") (class "Default")
      (node (ref "U3") (pin "12") (pinfunction "TDO/TDI_12") (pintype "passive+no_connect"))
    )
    (net (code "65") (name "/TMS_epic") (class "Default")
      (node (ref "U3") (pin "14") (pinfunction "TMS_14") (pintype "passive+no_connect"))
    )
    (net (code "66") (name "/TX_bt") (class "Default")
      (node (ref "U3") (pin "60") (pinfunction "UART0RX_60") (pintype "passive"))
      (node (ref "U5") (pin "11") (pinfunction "TX_11") (pintype "passive"))
    )
    (net (code "67") (name "/UART1RX_epic") (class "Default")
      (node (ref "U3") (pin "62") (pinfunction "UART1RX_62") (pintype "passive+no_connect"))
    )
    (net (code "68") (name "/UART1TX_epic") (class "Default")
      (node (ref "U3") (pin "61") (pinfunction "UART1TX_61") (pintype "passive+no_connect"))
    )
    (net (code "69") (name "/VREF+_epic") (class "Default")
      (node (ref "U3") (pin "27") (pinfunction "VREF+_27") (pintype "passive"))
    )
    (net (code "70") (name "/VRc") (class "Default")
      (node (ref "U6") (pin "8") (pinfunction "Rc_8") (pintype "passive"))
      (node (ref "U7") (pin "3") (pinfunction "W1_3") (pintype "passive"))
    )
    (net (code "71") (name "/VRg") (class "Default")
      (node (ref "U6") (pin "7") (pinfunction "Rg_7") (pintype "passive"))
      (node (ref "U8") (pin "3") (pinfunction "W1_3") (pintype "passive"))
    )
    (net (code "72") (name "/XOSC16IN") (class "Default")
      (node (ref "U3") (pin "64") (pinfunction "XOSC16IN_64") (pintype "passive+no_connect"))
    )
    (net (code "73") (name "/XOSC16OUT") (class "Default")
      (node (ref "U3") (pin "63") (pinfunction "XOSC16OUT_63") (pintype "passive+no_connect"))
    )
    (net (code "74") (name "/XT2IN_epic") (class "Default")
      (node (ref "C25") (pin "2") (pinfunction "2_2") (pintype "passive"))
      (node (ref "U3") (pin "11") (pinfunction "XT2IN_11") (pintype "passive"))
      (node (ref "Y1") (pin "2") (pinfunction "2_2") (pintype "passive"))
    )
    (net (code "75") (name "/XT2OUT_epic") (class "Default")
      (node (ref "C24") (pin "2") (pinfunction "2_2") (pintype "passive"))
      (node (ref "U3") (pin "10") (pinfunction "XT2OUT_10") (pintype "passive"))
      (node (ref "Y1") (pin "1") (pinfunction "1_1") (pintype "passive"))
    )
    (net (code "76") (name "DVDD_epic") (class "Default")
      (node (ref "C15") (pin "1") (pinfunction "1_1") (pintype "passive"))
      (node (ref "C16") (pin "1") (pinfunction "1_1") (pintype "passive"))
      (node (ref "C20") (pin "1") (pinfunction "1_1") (pintype "passive"))
      (node (ref "C26") (pin "1") (pinfunction "1_1") (pintype "passive"))
      (node (ref "C28") (pin "1") (pinfunction "1_1") (pintype "passive"))
      (node (ref "C4") (pin "1") (pinfunction "1_1") (pintype "passive"))
      (node (ref "C5") (pin "1") (pinfunction "1_1") (pintype "passive"))
      (node (ref "U3") (pin "17") (pinfunction "AVDD_17") (pintype "passive"))
      (node (ref "U3") (pin "28") (pinfunction "VEREF+_28") (pintype "passive"))
      (node (ref "U3") (pin "34") (pinfunction "FVDD_34") (pintype "passive"))
      (node (ref "U3") (pin "51") (pinfunction "RVDD_51") (pintype "passive"))
      (node (ref "U3") (pin "68") (pinfunction "DVDD_68") (pintype "passive"))
      (node (ref "U4") (pin "10") (pinfunction "VDD_10") (pintype "power_in"))
      (node (ref "U4") (pin "7") (pinfunction "VINB+_7") (pintype "passive"))
      (node (ref "U5") (pin "9") (pinfunction "VDD_9") (pintype "passive"))
      (node (ref "U6") (pin "10") (pinfunction "Vdd_10") (pintype "passive"))
      (node (ref "U7") (pin "5") (pinfunction "VDD_5") (pintype "passive"))
      (node (ref "U7") (pin "9") (pinfunction "AD0_9") (pintype "passive"))
      (node (ref "U8") (pin "5") (pinfunction "VDD_5") (pintype "passive"))
      (node (ref "U9") (pin "3") (pinfunction "Vdd_3") (pintype "passive"))
    )
    (net (code "77") (name "GND") (class "Default")
      (node (ref "C11") (pin "2") (pinfunction "2_2") (pintype "passive"))
      (node (ref "C12") (pin "2") (pinfunction "2_2") (pintype "passive"))
      (node (ref "C13") (pin "2") (pinfunction "2_2") (pintype "passive"))
      (node (ref "C14") (pin "2") (pinfunction "2_2") (pintype "passive"))
      (node (ref "C15") (pin "2") (pinfunction "2_2") (pintype "passive"))
      (node (ref "C16") (pin "2") (pinfunction "2_2") (pintype "passive"))
      (node (ref "C17") (pin "2") (pinfunction "2_2") (pintype "passive"))
      (node (ref "C18") (pin "2") (pinfunction "2_2") (pintype "passive"))
      (node (ref "C19") (pin "2") (pinfunction "2_2") (pintype "passive"))
      (node (ref "C2") (pin "1") (pinfunction "1_1") (pintype "passive"))
      (node (ref "C20") (pin "2") (pinfunction "2_2") (pintype "passive"))
      (node (ref "C24") (pin "1") (pinfunction "1_1") (pintype "passive"))
      (node (ref "C25") (pin "1") (pinfunction "1_1") (pintype "passive"))
      (node (ref "C26") (pin "2") (pinfunction "2_2") (pintype "passive"))
      (node (ref "C28") (pin "2") (pinfunction "2_2") (pintype "passive"))
      (node (ref "C4") (pin "2") (pinfunction "2_2") (pintype "passive"))
      (node (ref "C5") (pin "2") (pinfunction "2_2") (pintype "passive"))
      (node (ref "C7") (pin "2") (pinfunction "2_2") (pintype "passive"))
      (node (ref "C8") (pin "2") (pinfunction "2_2") (pintype "passive"))
      (node (ref "J1") (pin "1") (pinfunction "1_1") (pintype "passive"))
      (node (ref "MK1") (pin "2") (pinfunction "2_2") (pintype "passive"))
      (node (ref "R13") (pin "2") (pinfunction "2_2") (pintype "passive"))
      (node (ref "R17") (pin "2") (pinfunction "2_2") (pintype "passive"))
      (node (ref "R18") (pin "1") (pinfunction "1_1") (pintype "passive"))
      (node (ref "U1") (pin "4") (pinfunction "VSS_4") (pintype "power_in"))
      (node (ref "U10") (pin "3") (pinfunction "-_3") (pintype "passive"))
      (node (ref "U2") (pin "1") (pinfunction "GND_1") (pintype "power_in"))
      (node (ref "U3") (pin "1") (pinfunction "GND1_1") (pintype "passive"))
      (node (ref "U3") (pin "18") (pinfunction "AGND_18") (pintype "passive"))
      (node (ref "U3") (pin "29") (pinfunction "VEREF-_29") (pintype "passive"))
      (node (ref "U3") (pin "35") (pinfunction "GND2_35") (pintype "passive"))
      (node (ref "U3") (pin "52") (pinfunction "GND3_52") (pintype "passive"))
      (node (ref "U4") (pin "4") (pinfunction "VSS_4") (pintype "power_in"))
      (node (ref "U4") (pin "8") (pinfunction "VINB-_8") (pintype "passive"))
      (node (ref "U5") (pin "1") (pinfunction "GND_1") (pintype "passive"))
      (node (ref "U6") (pin "1") (pinfunction "GND_1") (pintype "passive"))
      (node (ref "U7") (pin "10") (pinfunction "AD1_10") (pintype "passive"))
      (node (ref "U7") (pin "11") (pinfunction "GND_11") (pintype "passive"))
      (node (ref "U7") (pin "12") (pinfunction "VSS_12") (pintype "passive"))
      (node (ref "U8") (pin "10") (pinfunction "AD1_10") (pintype "passive"))
      (node (ref "U8") (pin "11") (pinfunction "GND_11") (pintype "passive"))
      (node (ref "U8") (pin "12") (pinfunction "VSS_12") (pintype "passive"))
      (node (ref "U8") (pin "9") (pinfunction "AD0_9") (pintype "passive"))
      (node (ref "U9") (pin "11") (pinfunction "Thermal_11") (pintype "passive"))
      (node (ref "U9") (pin "7") (pinfunction "ST~{/M}N_7") (pintype "passive"))
      (node (ref "U9") (pin "8") (pinfunction "GND_8") (pintype "passive"))
    )
    (net (code "78") (name "Net-(C10-Pad1)") (class "Default")
      (node (ref "C10") (pin "1") (pinfunction "1_1") (pintype "passive"))
      (node (ref "R11") (pin "2") (pinfunction "2_2") (pintype "passive"))
    )
    (net (code "79") (name "Net-(C10-Pad2)") (class "Default")
      (node (ref "C10") (pin "2") (pinfunction "2_2") (pintype "passive"))
      (node (ref "MK1") (pin "1") (pinfunction "1_1") (pintype "passive"))
      (node (ref "R10") (pin "2") (pinfunction "2_2") (pintype "passive"))
    )
    (net (code "80") (name "Net-(C23-Pad1)") (class "Default")
      (node (ref "C23") (pin "1") (pinfunction "1_1") (pintype "passive"))
      (node (ref "J1") (pin "5") (pinfunction "5_5") (pintype "passive"))
      (node (ref "LS1") (pin "1") (pinfunction "1_1") (pintype "passive"))
    )
    (net (code "81") (name "Net-(C23-Pad2)") (class "Default")
      (node (ref "C23") (pin "2") (pinfunction "2_2") (pintype "passive"))
      (node (ref "J1") (pin "4") (pinfunction "4_4") (pintype "passive"))
      (node (ref "LS1") (pin "2") (pinfunction "2_2") (pintype "passive"))
    )
    (net (code "82") (name "Net-(C27-Pad1)") (class "Default")
      (node (ref "C27") (pin "1") (pinfunction "1_1") (pintype "passive"))
      (node (ref "R19") (pin "1") (pinfunction "1_1") (pintype "passive"))
    )
    (net (code "83") (name "Net-(R13-Pad1)") (class "Default")
      (node (ref "R13") (pin "1") (pinfunction "1_1") (pintype "passive"))
      (node (ref "R14") (pin "2") (pinfunction "2_2") (pintype "passive"))
      (node (ref "U10") (pin "1") (pinfunction "1_1") (pintype "passive"))
    )
    (net (code "84") (name "Net-(R16-Pad2)") (class "Default")
      (node (ref "R16") (pin "2") (pinfunction "2_2") (pintype "passive"))
      (node (ref "R7") (pin "2") (pinfunction "2_2") (pintype "passive"))
    )
    (net (code "85") (name "Net-(R21-Pad2)") (class "Default")
      (node (ref "R21") (pin "2") (pinfunction "2_2") (pintype "passive"))
      (node (ref "R25") (pin "1") (pinfunction "1_1") (pintype "passive"))
    )
    (net (code "86") (name "Net-(U1B-VINA+)") (class "Default")
      (node (ref "C9") (pin "2") (pinfunction "2_2") (pintype "passive"))
      (node (ref "D1") (pin "1") (pinfunction "1_1") (pintype "passive"))
      (node (ref "R9") (pin "1") (pinfunction "1_1") (pintype "passive"))
      (node (ref "U1") (pin "3") (pinfunction "VINA+_3") (pintype "passive"))
    )
    (net (code "87") (name "Net-(U1B-VINA-)") (class "Default")
      (node (ref "R24") (pin "1") (pinfunction "1_1") (pintype "passive"))
      (node (ref "R6") (pin "2") (pinfunction "2_2") (pintype "passive"))
      (node (ref "U1") (pin "2") (pinfunction "VINA-_2") (pintype "passive"))
    )
    (net (code "88") (name "Net-(U1B-VOUTA)") (class "Default")
      (node (ref "C9") (pin "1") (pinfunction "1_1") (pintype "passive"))
      (node (ref "R6") (pin "1") (pinfunction "1_1") (pintype "passive"))
      (node (ref "R8") (pin "2") (pinfunction "2_2") (pintype "passive"))
      (node (ref "R9") (pin "2") (pinfunction "2_2") (pintype "passive"))
      (node (ref "U1") (pin "1") (pinfunction "VOUTA_1") (pintype "passive"))
    )
    (net (code "89") (name "Net-(U1C-VINB+)") (class "Default")
      (node (ref "C1") (pin "2") (pinfunction "2_2") (pintype "passive"))
      (node (ref "D1") (pin "2") (pinfunction "2_2") (pintype "passive"))
      (node (ref "R1") (pin "1") (pinfunction "1_1") (pintype "passive"))
      (node (ref "U1") (pin "5") (pinfunction "VINB+_5") (pintype "passive"))
    )
    (net (code "90") (name "Net-(U1C-VINB-)") (class "Default")
      (node (ref "R23") (pin "2") (pinfunction "2_2") (pintype "passive"))
      (node (ref "R24") (pin "2") (pinfunction "2_2") (pintype "passive"))
      (node (ref "U1") (pin "6") (pinfunction "VINB-_6") (pintype "passive"))
    )
    (net (code "91") (name "Net-(U1C-VOUTB)") (class "Default")
      (node (ref "C1") (pin "1") (pinfunction "1_1") (pintype "passive"))
      (node (ref "R1") (pin "2") (pinfunction "2_2") (pintype "passive"))
      (node (ref "R22") (pin "2") (pinfunction "2_2") (pintype "passive"))
      (node (ref "R23") (pin "1") (pinfunction "1_1") (pintype "passive"))
      (node (ref "U1") (pin "7") (pinfunction "VOUTB_7") (pintype "passive"))
    )
    (net (code "92") (name "Net-(U4A-~{SHDN}_A)") (class "Default")
      (node (ref "R26") (pin "1") (pinfunction "1_1") (pintype "passive"))
      (node (ref "U4") (pin "5") (pinfunction "~{SHDN}_A_5") (pintype "passive"))
    )
    (net (code "93") (name "Net-(U4A-~{SHDN}_B)") (class "Default")
      (node (ref "R27") (pin "1") (pinfunction "1_1") (pintype "passive"))
      (node (ref "U4") (pin "6") (pinfunction "~{SHDN}_B_6") (pintype "passive"))
    )
    (net (code "94") (name "Net-(U4B-VINA-)") (class "Default")
      (node (ref "C21") (pin "2") (pinfunction "2_2") (pintype "passive"))
      (node (ref "R16") (pin "1") (pinfunction "1_1") (pintype "passive"))
      (node (ref "R21") (pin "1") (pinfunction "1_1") (pintype "passive"))
      (node (ref "U4") (pin "2") (pinfunction "VINA-_2") (pintype "passive"))
    )
    (net (code "95") (name "Net-(U4B-VOUTA)") (class "Default")
      (node (ref "C21") (pin "1") (pinfunction "1_1") (pintype "passive"))
      (node (ref "R20") (pin "1") (pinfunction "1_1") (pintype "passive"))
      (node (ref "R25") (pin "2") (pinfunction "2_2") (pintype "passive"))
      (node (ref "U4") (pin "1") (pinfunction "VOUTA_1") (pintype "passive"))
    )
    (net (code "96") (name "Net-(U4C-VOUTB)") (class "Default")
      (node (ref "R15") (pin "1") (pinfunction "1_1") (pintype "passive"))
      (node (ref "U4") (pin "9") (pinfunction "VOUTB_9") (pintype "passive"))
    )
    (net (code "97") (name "Net-(U6-BUFout)") (class "Default")
      (node (ref "C6") (pin "1") (pinfunction "1_1") (pintype "passive"))
      (node (ref "U6") (pin "4") (pinfunction "BUFout_4") (pintype "passive"))
    )
    (net (code "98") (name "Net-(U6-Cavg)") (class "Default")
      (node (ref "C17") (pin "1") (pinfunction "1_1") (pintype "passive"))
      (node (ref "U6") (pin "6") (pinfunction "Cavg_6") (pintype "passive"))
    )
    (net (code "99") (name "Net-(U6-IN)") (class "Default")
      (node (ref "C11") (pin "1") (pinfunction "1_1") (pintype "passive"))
      (node (ref "R11") (pin "1") (pinfunction "1_1") (pintype "passive"))
      (node (ref "U6") (pin "5") (pinfunction "IN_5") (pintype "passive"))
    )
    (net (code "100") (name "Net-(U6-OUT)") (class "Default")
      (node (ref "R7") (pin "1") (pinfunction "1_1") (pintype "passive"))
      (node (ref "U6") (pin "9") (pinfunction "OUT_9") (pintype "passive"))
    )
    (net (code "101") (name "Net-(U6-VCAin)") (class "Default")
      (node (ref "C6") (pin "2") (pinfunction "2_2") (pintype "passive"))
      (node (ref "U6") (pin "2") (pinfunction "VCAin_2") (pintype "passive"))
    )
    (net (code "102") (name "Net-(U9-Bypass)") (class "Default")
      (node (ref "C18") (pin "1") (pinfunction "1_1") (pintype "passive"))
      (node (ref "U9") (pin "4") (pinfunction "Bypass_4") (pintype "passive"))
    )
    (net (code "103") (name "Net-(U9-FILT_CAP)") (class "Default")
      (node (ref "C19") (pin "1") (pinfunction "1_1") (pintype "passive"))
      (node (ref "U9") (pin "1") (pinfunction "FILT_CAP_1") (pintype "passive"))
    )
    (net (code "104") (name "Net-(U9-LO)") (class "Default")
      (node (ref "J1") (pin "3") (pinfunction "3_3") (pintype "passive"))
      (node (ref "U9") (pin "10") (pinfunction "LO_10") (pintype "passive"))
    )
    (net (code "105") (name "Net-(U9-Lin)") (class "Default")
      (node (ref "R19") (pin "2") (pinfunction "2_2") (pintype "passive"))
      (node (ref "U9") (pin "9") (pinfunction "Lin_9") (pintype "passive"))
    )
    (net (code "106") (name "Net-(U9-RO)") (class "Default")
      (node (ref "J1") (pin "2") (pinfunction "2_2") (pintype "passive"))
      (node (ref "U9") (pin "6") (pinfunction "RO_6") (pintype "passive"))
    )
    (net (code "107") (name "Net-(U9-Rin)") (class "Default")
      (node (ref "R18") (pin "2") (pinfunction "2_2") (pintype "passive"))
      (node (ref "U9") (pin "5") (pinfunction "Rin_5") (pintype "passive"))
    )
    (net (code "108") (name "unconnected-(U7-A1-Pad2)") (class "Default")
      (node (ref "U7") (pin "2") (pinfunction "A1_2") (pintype "passive+no_connect"))
    )
    (net (code "109") (name "unconnected-(U7-A2-Pad16)") (class "Default")
      (node (ref "U7") (pin "16") (pinfunction "A2_16") (pintype "passive+no_connect"))
    )
    (net (code "110") (name "unconnected-(U7-B2-Pad14)") (class "Default")
      (node (ref "U7") (pin "14") (pinfunction "B2_14") (pintype "passive+no_connect"))
    )
    (net (code "111") (name "unconnected-(U7-O1-Pad1)") (class "Default")
      (node (ref "U7") (pin "1") (pinfunction "O1_1") (pintype "passive+no_connect"))
    )
    (net (code "112") (name "unconnected-(U7-O2-Pad13)") (class "Default")
      (node (ref "U7") (pin "13") (pinfunction "O2_13") (pintype "passive+no_connect"))
    )
    (net (code "113") (name "unconnected-(U7-W2-Pad15)") (class "Default")
      (node (ref "U7") (pin "15") (pinfunction "W2_15") (pintype "passive+no_connect"))
    )
    (net (code "114") (name "unconnected-(U8-A1-Pad2)") (class "Default")
      (node (ref "U8") (pin "2") (pinfunction "A1_2") (pintype "passive+no_connect"))
    )
    (net (code "115") (name "unconnected-(U8-A2-Pad16)") (class "Default")
      (node (ref "U8") (pin "16") (pinfunction "A2_16") (pintype "passive+no_connect"))
    )
    (net (code "116") (name "unconnected-(U8-B2-Pad14)") (class "Default")
      (node (ref "U8") (pin "14") (pinfunction "B2_14") (pintype "passive+no_connect"))
    )
    (net (code "117") (name "unconnected-(U8-O1-Pad1)") (class "Default")
      (node (ref "U8") (pin "1") (pinfunction "O1_1") (pintype "passive+no_connect"))
    )
    (net (code "118") (name "unconnected-(U8-O2-Pad13)") (class "Default")
      (node (ref "U8") (pin "13") (pinfunction "O2_13") (pintype "passive+no_connect"))
    )
    (net (code "119") (name "unconnected-(U8-W2-Pad15)") (class "Default")
      (node (ref "U8") (pin "15") (pinfunction "W2_15") (pintype "passive+no_connect"))
    )
  )
)
